# SCH_Curtain-Opener-try1_2026-10-07.net
KiCad netlist of a schematic drawn in EasyEDA
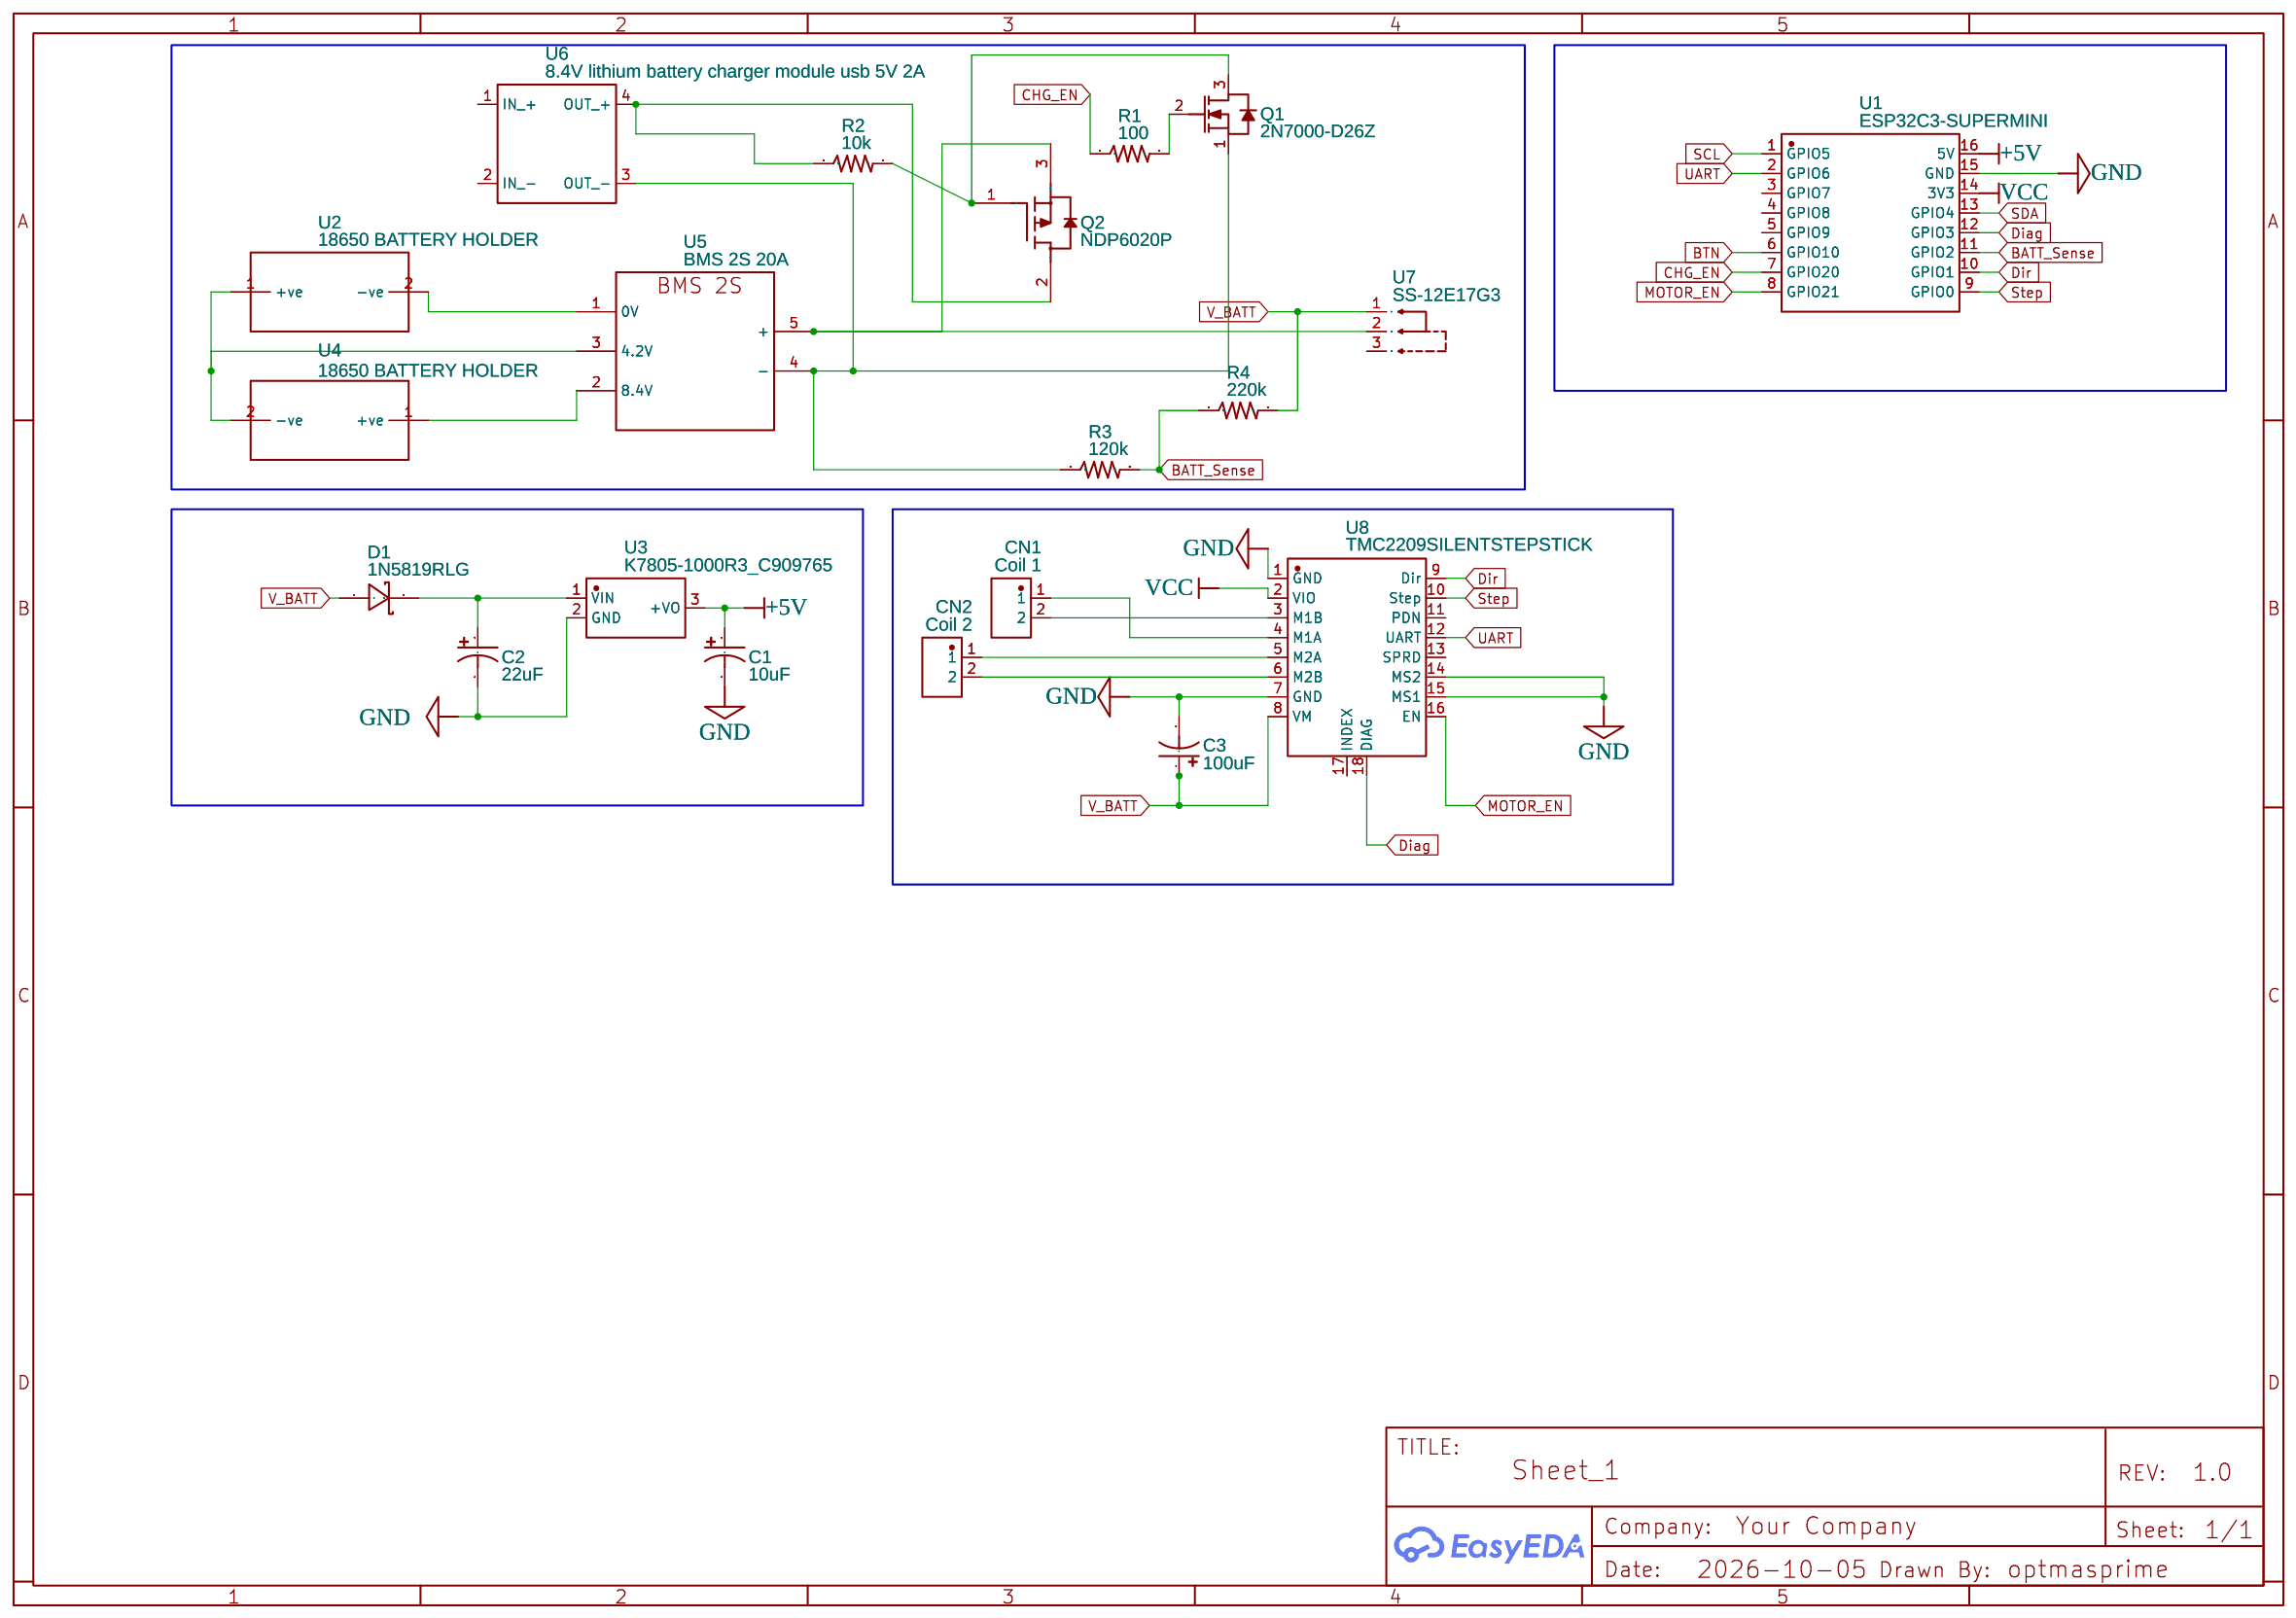
[diagram p0: schematic sheet]

(export (version "E")
  (design (tool "Eeschema 10.0.6"))
  (components
    (comp (ref "C1") (value "10uF") (libsource (lib "") (part "10UF-25V-20%(PTH)KIT")))
    (comp (ref "C2") (value "22uF") (libsource (lib "") (part "10UF-25V-20%(PTH)KIT_2")))
    (comp (ref "C3") (value "100uF") (libsource (lib "") (part "10UF-25V-20%(PTH)KIT_1")))
    (comp (ref "CN1")
      (value "Coil 1")
      (fields (field (name "Manufacturer Part") "MG129-5.08-2P"))
      (libsource (lib "") (part "MG129-5.08-2P"))
    )
    (comp (ref "CN2")
      (value "Coil 2")
      (fields (field (name "Manufacturer Part") "MG129-5.08-2P"))
      (libsource (lib "") (part "MG129-5.08-2P"))
    )
    (comp (ref "D1")
      (value "1N5819RLG")
      (fields (field (name "Manufacturer") "onsemi(安森美)"))
      (libsource (lib "") (part "1N5819RLG"))
    )
    (comp (ref "Q1")
      (value "2N7000-D26Z")
      (fields (field (name "Manufacturer") "onsemi(安森美)"))
      (libsource (lib "") (part "2N7000-D26Z"))
    )
    (comp (ref "Q2")
      (value "NDP6020P")
      (fields (field (name "Manufacturer") "onsemi(安森美)"))
      (libsource (lib "") (part "NDP6020P"))
    )
    (comp (ref "R1") (value "100") (libsource (lib "") (part "10KOHM-1_4W5%(PTH)HORIZ-KIT")))
    (comp (ref "R2") (value "10k") (libsource (lib "") (part "10KOHM-1_4W5%(PTH)HORIZ-KIT")))
    (comp (ref "R3") (value "120k") (libsource (lib "") (part "10KOHM-1_4W5%(PTH)HORIZ-KIT")))
    (comp (ref "R4") (value "220k") (libsource (lib "") (part "10KOHM-1_4W5%(PTH)HORIZ-KIT")))
    (comp (ref "U1")
      (value "ESP32C3-SUPERMINI")
      (fields (field (name "Manufacturer Part") "ESP32C3-SuperMini"))
      (libsource (lib "") (part "ESP32C3-SUPERMINI"))
    )
    (comp (ref "U2") (value "18650 BATTERY HOLDER") (libsource (lib "") (part "18650 BATTERY HOLDER_1")))
    (comp (ref "U3")
      (value "K7805-1000R3_C909765")
      (fields (field (name "Manufacturer Part") "K7805-1000R3") (field (name "Manufacturer") "DEXU(德旭电子)"))
      (libsource (lib "") (part "K7805-1000R3_C909765"))
    )
    (comp (ref "U4") (value "18650 BATTERY HOLDER") (libsource (lib "") (part "18650 BATTERY HOLDER")))
    (comp (ref "U5")
      (value "BMS 2S 20A")
      (fields (field (name "Manufacturer Part") "BMS 2S 8.4V, 20A"))
      (libsource (lib "") (part "BMS 2S 20A"))
    )
    (comp (ref "U6")
      (value "8.4V lithium battery charger module usb 5V 2A")
      (libsource (lib "") (part "8.4V lithium battery charger module usb 5V 2A"))
    )
    (comp (ref "U7")
      (value "SS-12E17G3")
      (fields (field (name "Manufacturer") "HOOYA(皓宇电子)"))
      (libsource (lib "") (part "SS-12E17G3"))
    )
    (comp (ref "U8")
      (value "TMC2209SILENTSTEPSTICK")
      (fields (field (name "Manufacturer") "TRINAMIC"))
      (libsource (lib "") (part "TMC2209SILENTSTEPSTICK"))
    )
  )
  (nets
    (net (code "1") (name "+5V") (class "Default")
      (node (ref "C1") (pin "1") (pinfunction "+_1") (pintype "unspecified"))
      (node (ref "U1") (pin "16") (pinfunction "5V_16") (pintype "unspecified"))
      (node (ref "U3") (pin "3") (pinfunction "+VO_3") (pintype "unspecified"))
    )
    (net (code "2") (name "BATT_Sense") (class "Default")
      (node (ref "R3") (pin "P$2") (pinfunction "2_P$2") (pintype "unspecified"))
      (node (ref "R4") (pin "P$1") (pinfunction "1_P$1") (pintype "unspecified"))
      (node (ref "U1") (pin "11") (pinfunction "GPIO2_11") (pintype "unspecified"))
    )
    (net (code "3") (name "BTN") (class "Default")
      (node (ref "U1") (pin "6") (pinfunction "GPIO10_6") (pintype "unspecified"))
    )
    (net (code "4") (name "CHG_EN") (class "Default")
      (node (ref "R1") (pin "P$1") (pinfunction "1_P$1") (pintype "unspecified"))
      (node (ref "U1") (pin "7") (pinfunction "GPIO20_7") (pintype "unspecified"))
    )
    (net (code "5") (name "Diag") (class "Default")
      (node (ref "U1") (pin "12") (pinfunction "GPIO3_12") (pintype "unspecified"))
      (node (ref "U8") (pin "18") (pinfunction "DIAG_18") (pintype "unspecified"))
    )
    (net (code "6") (name "Dir") (class "Default")
      (node (ref "U1") (pin "10") (pinfunction "GPIO1_10") (pintype "unspecified"))
      (node (ref "U8") (pin "9") (pinfunction "Dir_9") (pintype "unspecified"))
    )
    (net (code "7") (name "GND") (class "Default")
      (node (ref "C1") (pin "2") (pinfunction "-_2") (pintype "unspecified"))
      (node (ref "C2") (pin "2") (pinfunction "-_2") (pintype "unspecified"))
      (node (ref "C3") (pin "2") (pinfunction "-_2") (pintype "unspecified"))
      (node (ref "U1") (pin "15") (pinfunction "GND_15") (pintype "unspecified"))
      (node (ref "U3") (pin "2") (pinfunction "GND_2") (pintype "unspecified"))
      (node (ref "U8") (pin "1") (pinfunction "GND_1") (pintype "unspecified"))
      (node (ref "U8") (pin "14") (pinfunction "MS2_14") (pintype "unspecified"))
      (node (ref "U8") (pin "15") (pinfunction "MS1_15") (pintype "unspecified"))
      (node (ref "U8") (pin "7") (pinfunction "GND_7") (pintype "unspecified"))
    )
    (net (code "8") (name "MOTOR_EN") (class "Default")
      (node (ref "U1") (pin "8") (pinfunction "GPIO21_8") (pintype "unspecified"))
      (node (ref "U8") (pin "16") (pinfunction "EN_16") (pintype "unspecified"))
    )
    (net (code "9") (name "Net-(C2-+)") (class "Default")
      (node (ref "C2") (pin "1") (pinfunction "+_1") (pintype "unspecified"))
      (node (ref "D1") (pin "1") (pinfunction "C_1") (pintype "unspecified"))
      (node (ref "U3") (pin "1") (pinfunction "VIN_1") (pintype "unspecified"))
    )
    (net (code "10") (name "Net-(Q1-D)") (class "Default")
      (node (ref "Q1") (pin "3") (pinfunction "D_3") (pintype "unspecified"))
      (node (ref "Q2") (pin "1") (pinfunction "G_1") (pintype "unspecified"))
      (node (ref "R2") (pin "P$2") (pinfunction "2_P$2") (pintype "unspecified"))
    )
    (net (code "11") (name "Net-(Q1-G)") (class "Default")
      (node (ref "Q1") (pin "2") (pinfunction "G_2") (pintype "unspecified"))
      (node (ref "R1") (pin "P$2") (pinfunction "2_P$2") (pintype "unspecified"))
    )
    (net (code "12") (name "Net-(Q1-S)") (class "Default")
      (node (ref "Q1") (pin "1") (pinfunction "S_1") (pintype "unspecified"))
      (node (ref "R3") (pin "P$1") (pinfunction "1_P$1") (pintype "unspecified"))
      (node (ref "U5") (pin "4") (pinfunction "-_4") (pintype "passive"))
      (node (ref "U6") (pin "3") (pinfunction "OUT_-_3") (pintype "unspecified"))
    )
    (net (code "13") (name "Net-(Q2-D)") (class "Default")
      (node (ref "Q2") (pin "2") (pinfunction "D_2") (pintype "unspecified"))
      (node (ref "R2") (pin "P$1") (pinfunction "1_P$1") (pintype "unspecified"))
      (node (ref "U6") (pin "4") (pinfunction "OUT_+_4") (pintype "unspecified"))
    )
    (net (code "14") (name "Net-(Q2-S)") (class "Default")
      (node (ref "Q2") (pin "3") (pinfunction "S_3") (pintype "unspecified"))
      (node (ref "U5") (pin "5") (pinfunction "+_5") (pintype "passive"))
      (node (ref "U7") (pin "2") (pinfunction "2_2") (pintype "unspecified"))
    )
    (net (code "15") (name "Net-(U2-+ve)") (class "Default")
      (node (ref "U2") (pin "1") (pinfunction "+ve_1") (pintype "unspecified"))
      (node (ref "U4") (pin "2") (pinfunction "-ve_2") (pintype "unspecified"))
      (node (ref "U5") (pin "3") (pinfunction "4.2V_3") (pintype "output"))
    )
    (net (code "16") (name "Net-(U2--ve)") (class "Default")
      (node (ref "U2") (pin "2") (pinfunction "-ve_2") (pintype "unspecified"))
      (node (ref "U5") (pin "1") (pinfunction "0V_1") (pintype "output"))
    )
    (net (code "17") (name "Net-(U4-+ve)") (class "Default")
      (node (ref "U4") (pin "1") (pinfunction "+ve_1") (pintype "unspecified"))
      (node (ref "U5") (pin "2") (pinfunction "8.4V_2") (pintype "output"))
    )
    (net (code "18") (name "Net-(U8-M1A)") (class "Default")
      (node (ref "CN1") (pin "1") (pinfunction "1_1") (pintype "unspecified"))
      (node (ref "U8") (pin "4") (pinfunction "M1A_4") (pintype "unspecified"))
    )
    (net (code "19") (name "Net-(U8-M1B)") (class "Default")
      (node (ref "CN1") (pin "2") (pinfunction "2_2") (pintype "unspecified"))
      (node (ref "U8") (pin "3") (pinfunction "M1B_3") (pintype "unspecified"))
    )
    (net (code "20") (name "Net-(U8-M2A)") (class "Default")
      (node (ref "CN2") (pin "1") (pinfunction "1_1") (pintype "unspecified"))
      (node (ref "U8") (pin "5") (pinfunction "M2A_5") (pintype "unspecified"))
    )
    (net (code "21") (name "Net-(U8-M2B)") (class "Default")
      (node (ref "CN2") (pin "2") (pinfunction "2_2") (pintype "unspecified"))
      (node (ref "U8") (pin "6") (pinfunction "M2B_6") (pintype "unspecified"))
    )
    (net (code "22") (name "SCL") (class "Default")
      (node (ref "U1") (pin "1") (pinfunction "GPIO5_1") (pintype "unspecified"))
    )
    (net (code "23") (name "SDA") (class "Default")
      (node (ref "U1") (pin "13") (pinfunction "GPIO4_13") (pintype "unspecified"))
    )
    (net (code "24") (name "Step") (class "Default")
      (node (ref "U1") (pin "9") (pinfunction "GPIO0_9") (pintype "unspecified"))
      (node (ref "U8") (pin "10") (pinfunction "Step_10") (pintype "unspecified"))
    )
    (net (code "25") (name "UART") (class "Default")
      (node (ref "U1") (pin "2") (pinfunction "GPIO6_2") (pintype "unspecified"))
      (node (ref "U8") (pin "12") (pinfunction "UART_12") (pintype "unspecified"))
    )
    (net (code "26") (name "VCC") (class "Default")
      (node (ref "U1") (pin "14") (pinfunction "3V3_14") (pintype "unspecified"))
      (node (ref "U8") (pin "2") (pinfunction "VIO_2") (pintype "unspecified"))
    )
    (net (code "27") (name "V_BATT") (class "Default")
      (node (ref "C3") (pin "1") (pinfunction "+_1") (pintype "unspecified"))
      (node (ref "D1") (pin "2") (pinfunction "A_2") (pintype "unspecified"))
      (node (ref "R4") (pin "P$2") (pinfunction "2_P$2") (pintype "unspecified"))
      (node (ref "U7") (pin "1") (pinfunction "1_1") (pintype "unspecified"))
      (node (ref "U8") (pin "8") (pinfunction "VM_8") (pintype "unspecified"))
    )
    (net (code "28") (name "unconnected-(U1-GPIO7-Pad3)") (class "Default")
      (node (ref "U1") (pin "3") (pinfunction "GPIO7_3") (pintype "unspecified"))
    )
    (net (code "29") (name "unconnected-(U1-GPIO8-Pad4)") (class "Default")
      (node (ref "U1") (pin "4") (pinfunction "GPIO8_4") (pintype "unspecified"))
    )
    (net (code "30") (name "unconnected-(U1-GPIO9-Pad5)") (class "Default")
      (node (ref "U1") (pin "5") (pinfunction "GPIO9_5") (pintype "unspecified"))
    )
    (net (code "31") (name "unconnected-(U6-IN_+-Pad1)") (class "Default")
      (node (ref "U6") (pin "1") (pinfunction "IN_+_1") (pintype "unspecified"))
    )
    (net (code "32") (name "unconnected-(U6-IN_--Pad2)") (class "Default")
      (node (ref "U6") (pin "2") (pinfunction "IN_-_2") (pintype "unspecified"))
    )
    (net (code "33") (name "unconnected-(U7-Pad3)") (class "Default")
      (node (ref "U7") (pin "3") (pinfunction "3_3") (pintype "unspecified"))
    )
    (net (code "34") (name "unconnected-(U8-INDEX-Pad17)") (class "Default")
      (node (ref "U8") (pin "17") (pinfunction "INDEX_17") (pintype "unspecified"))
    )
    (net (code "35") (name "unconnected-(U8-PDN-Pad11)") (class "Default")
      (node (ref "U8") (pin "11") (pinfunction "PDN_11") (pintype "unspecified"))
    )
    (net (code "36") (name "unconnected-(U8-SPRD-Pad13)") (class "Default")
      (node (ref "U8") (pin "13") (pinfunction "SPRD_13") (pintype "unspecified"))
    )
  )
)
